# ADC_01_HYB.net
KiCad netlist of a schematic drawn in Altium Designer
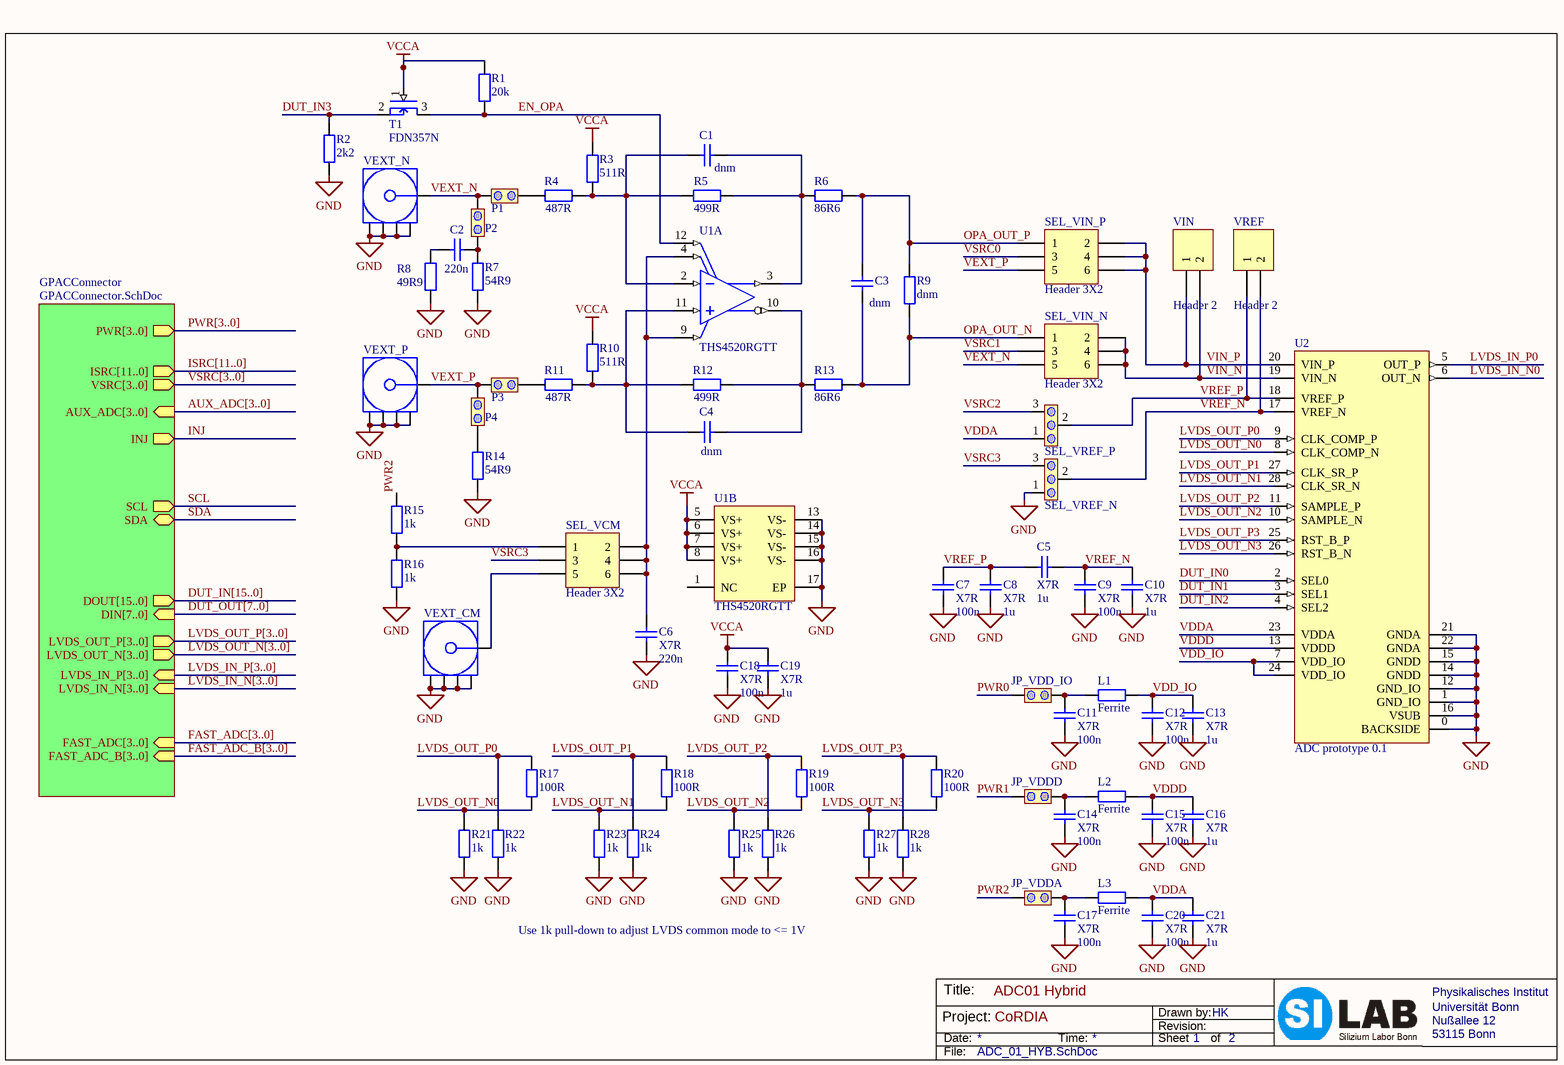
[diagram p0: ADC_01_HYB.SchDoc]

(export (version "E")
  (design (tool "Eeschema 10.0.6"))
  (components
    (comp (ref "C1")
      (value "dnm")
      (footprint "C0603_imp_N")
      (description "Capacitor")
      (fields (field (name "Comment") "X7R") (field (name "PUBLISHER") "Silab J.S."))
      (libsource (lib "Silab_Lib") (part "C"))
    )
    (comp (ref "C2")
      (value "220n")
      (footprint "C0603_imp_N")
      (description "Capacitor")
      (fields (field (name "Comment") "X7R") (field (name "PUBLISHER") "Silab J.S."))
      (libsource (lib "Silab_Lib") (part "C"))
    )
    (comp (ref "C3")
      (value "dnm")
      (footprint "C0603_imp_N")
      (description "Capacitor")
      (fields (field (name "Comment") "X7R") (field (name "PUBLISHER") "Silab J.S."))
      (libsource (lib "Silab_Lib") (part "C"))
    )
    (comp (ref "C4")
      (value "dnm")
      (footprint "C0603_imp_N")
      (description "Capacitor")
      (fields (field (name "Comment") "X7R") (field (name "PUBLISHER") "Silab J.S."))
      (libsource (lib "Silab_Lib") (part "C"))
    )
    (comp (ref "C5")
      (value "X7R")
      (footprint "C0603_imp_N")
      (description "Capacitor")
      (fields (field (name "ALTIUM_VALUE") "1u") (field (name "PUBLISHER") "Silab J.S."))
      (libsource (lib "Silab_Lib") (part "C"))
    )
    (comp (ref "C6")
      (value "X7R")
      (footprint "C0603_imp_N")
      (description "Capacitor")
      (fields (field (name "ALTIUM_VALUE") "220n") (field (name "PUBLISHER") "Silab J.S."))
      (libsource (lib "Silab_Lib") (part "C"))
    )
    (comp (ref "C7")
      (value "X7R")
      (footprint "C0603_imp_N")
      (description "Capacitor")
      (fields (field (name "ALTIUM_VALUE") "100n") (field (name "PUBLISHER") "Silab J.S."))
      (libsource (lib "Silab_Lib") (part "C"))
    )
    (comp (ref "C8")
      (value "X7R")
      (footprint "C0603_imp_N")
      (description "Capacitor")
      (fields (field (name "ALTIUM_VALUE") "1u") (field (name "PUBLISHER") "Silab J.S."))
      (libsource (lib "Silab_Lib") (part "C"))
    )
    (comp (ref "C9")
      (value "X7R")
      (footprint "C0603_imp_N")
      (description "Capacitor")
      (fields (field (name "ALTIUM_VALUE") "100n") (field (name "PUBLISHER") "Silab J.S."))
      (libsource (lib "Silab_Lib") (part "C"))
    )
    (comp (ref "C10")
      (value "X7R")
      (footprint "C0603_imp_N")
      (description "Capacitor")
      (fields (field (name "ALTIUM_VALUE") "1u") (field (name "PUBLISHER") "Silab J.S."))
      (libsource (lib "Silab_Lib") (part "C"))
    )
    (comp (ref "C11")
      (value "X7R")
      (footprint "C0603_imp_N")
      (description "Capacitor")
      (fields (field (name "ALTIUM_VALUE") "100n") (field (name "PUBLISHER") "Silab J.S."))
      (libsource (lib "Silab_Lib") (part "C"))
    )
    (comp (ref "C12")
      (value "X7R")
      (footprint "C0603_imp_N")
      (description "Capacitor")
      (fields (field (name "ALTIUM_VALUE") "100n") (field (name "PUBLISHER") "Silab J.S."))
      (libsource (lib "Silab_Lib") (part "C"))
    )
    (comp (ref "C13")
      (value "X7R")
      (footprint "C0603_imp_N")
      (description "Capacitor")
      (fields (field (name "ALTIUM_VALUE") "1u") (field (name "PUBLISHER") "Silab J.S."))
      (libsource (lib "Silab_Lib") (part "C"))
    )
    (comp (ref "C14")
      (value "X7R")
      (footprint "C0603_imp_N")
      (description "Capacitor")
      (fields (field (name "ALTIUM_VALUE") "100n") (field (name "PUBLISHER") "Silab J.S."))
      (libsource (lib "Silab_Lib") (part "C"))
    )
    (comp (ref "C15")
      (value "X7R")
      (footprint "C0603_imp_N")
      (description "Capacitor")
      (fields (field (name "ALTIUM_VALUE") "100n") (field (name "PUBLISHER") "Silab J.S."))
      (libsource (lib "Silab_Lib") (part "C"))
    )
    (comp (ref "C16")
      (value "X7R")
      (footprint "C0603_imp_N")
      (description "Capacitor")
      (fields (field (name "ALTIUM_VALUE") "1u") (field (name "PUBLISHER") "Silab J.S."))
      (libsource (lib "Silab_Lib") (part "C"))
    )
    (comp (ref "C17")
      (value "X7R")
      (footprint "C0603_imp_N")
      (description "Capacitor")
      (fields (field (name "ALTIUM_VALUE") "100n") (field (name "PUBLISHER") "Silab J.S."))
      (libsource (lib "Silab_Lib") (part "C"))
    )
    (comp (ref "C18")
      (value "X7R")
      (footprint "C0603_imp_N")
      (description "Capacitor")
      (fields (field (name "ALTIUM_VALUE") "100n") (field (name "PUBLISHER") "Silab J.S."))
      (libsource (lib "Silab_Lib") (part "C"))
    )
    (comp (ref "C19")
      (value "X7R")
      (footprint "C0603_imp_N")
      (description "Capacitor")
      (fields (field (name "ALTIUM_VALUE") "1u") (field (name "PUBLISHER") "Silab J.S."))
      (libsource (lib "Silab_Lib") (part "C"))
    )
    (comp (ref "C20")
      (value "X7R")
      (footprint "C0603_imp_N")
      (description "Capacitor")
      (fields (field (name "ALTIUM_VALUE") "100n") (field (name "PUBLISHER") "Silab J.S."))
      (libsource (lib "Silab_Lib") (part "C"))
    )
    (comp (ref "C21")
      (value "X7R")
      (footprint "C0603_imp_N")
      (description "Capacitor")
      (fields (field (name "ALTIUM_VALUE") "1u") (field (name "PUBLISHER") "Silab J.S."))
      (libsource (lib "Silab_Lib") (part "C"))
    )
    (comp (ref "JP_VDDA")
      (value "-")
      (footprint "CON 1x2 std")
      (description "Jumper, Solderbridge 1x2")
      (fields (field (name "PUBLISHER") "Silab C.H."))
      (libsource (lib "Silab_Lib") (part "JUMPER 1X2S"))
    )
    (comp (ref "JP_VDDD")
      (value "-")
      (footprint "CON 1x2 std")
      (description "Jumper, Solderbridge 1x2")
      (fields (field (name "PUBLISHER") "Silab C.H."))
      (libsource (lib "Silab_Lib") (part "JUMPER 1X2S"))
    )
    (comp (ref "JP_VDD_IO")
      (value "-")
      (footprint "CON 1x2 std")
      (description "Jumper, Solderbridge 1x2")
      (fields (field (name "PUBLISHER") "Silab C.H."))
      (libsource (lib "Silab_Lib") (part "JUMPER 1X2S"))
    )
    (comp (ref "L1")
      (value "Ferrite")
      (footprint "R0603_imp_N")
      (description "SMD Chip Resistor")
      (fields (field (name "Comment") "R") (field (name "PUBLISHER") "Silab J.S."))
      (libsource (lib "Silab_Lib") (part "R"))
    )
    (comp (ref "L2")
      (value "Ferrite")
      (footprint "R0603_imp_N")
      (description "SMD Chip Resistor")
      (fields (field (name "Comment") "R") (field (name "PUBLISHER") "Silab J.S."))
      (libsource (lib "Silab_Lib") (part "R"))
    )
    (comp (ref "L3")
      (value "Ferrite")
      (footprint "R0603_imp_N")
      (description "SMD Chip Resistor")
      (fields (field (name "Comment") "R") (field (name "PUBLISHER") "Silab J.S."))
      (libsource (lib "Silab_Lib") (part "R"))
    )
    (comp (ref "P1")
      (value "-")
      (footprint "CON 1x2 std")
      (description "Jumper, Solderbridge 1x2")
      (fields (field (name "PUBLISHER") "Silab C.H."))
      (libsource (lib "") (part "JUMPER 1X2S_2"))
    )
    (comp (ref "P2")
      (value "-")
      (footprint "CON 1x2 std")
      (description "Jumper, Solderbridge 1x2")
      (fields (field (name "PUBLISHER") "Silab C.H."))
      (libsource (lib "") (part "JUMPER 1X2S_1"))
    )
    (comp (ref "P3")
      (value "-")
      (footprint "CON 1x2 std")
      (description "Jumper, Solderbridge 1x2")
      (fields (field (name "PUBLISHER") "Silab C.H."))
      (libsource (lib "") (part "JUMPER 1X2S_2"))
    )
    (comp (ref "P4")
      (value "-")
      (footprint "CON 1x2 std")
      (description "Jumper, Solderbridge 1x2")
      (fields (field (name "PUBLISHER") "Silab C.H."))
      (libsource (lib "") (part "JUMPER 1X2S_1"))
    )
    (comp (ref "R1")
      (value "20k")
      (footprint "R0603_imp_N")
      (description "SMD Chip Resistor")
      (fields (field (name "Comment") "R") (field (name "PUBLISHER") "Silab J.S."))
      (libsource (lib "Silab_Lib") (part "R"))
    )
    (comp (ref "R2")
      (value "2k2")
      (footprint "R0603_imp_N")
      (description "SMD Chip Resistor")
      (fields (field (name "Comment") "R") (field (name "PUBLISHER") "Silab J.S."))
      (libsource (lib "Silab_Lib") (part "R"))
    )
    (comp (ref "R3")
      (value "511R")
      (footprint "R0603_imp_N")
      (description "SMD Chip Resistor")
      (fields (field (name "Comment") "R") (field (name "PUBLISHER") "Silab J.S."))
      (libsource (lib "Silab_Lib") (part "R"))
    )
    (comp (ref "R4")
      (value "487R")
      (footprint "R0603_imp_N")
      (description "SMD Chip Resistor")
      (fields (field (name "Comment") "R") (field (name "PUBLISHER") "Silab J.S."))
      (libsource (lib "Silab_Lib") (part "R"))
    )
    (comp (ref "R5")
      (value "499R")
      (footprint "R0603_imp_N")
      (description "SMD Chip Resistor")
      (fields (field (name "Comment") "R") (field (name "PUBLISHER") "Silab J.S."))
      (libsource (lib "Silab_Lib") (part "R"))
    )
    (comp (ref "R6")
      (value "86R6")
      (footprint "R0603_imp_N")
      (description "SMD Chip Resistor")
      (fields (field (name "Comment") "R") (field (name "PUBLISHER") "Silab J.S."))
      (libsource (lib "Silab_Lib") (part "R"))
    )
    (comp (ref "R7")
      (value "54R9")
      (footprint "R0603_imp_N")
      (description "SMD Chip Resistor")
      (fields (field (name "Comment") "R") (field (name "PUBLISHER") "Silab J.S."))
      (libsource (lib "Silab_Lib") (part "R"))
    )
    (comp (ref "R8")
      (value "49R9")
      (footprint "R0603_imp_N")
      (description "SMD Chip Resistor")
      (fields (field (name "Comment") "R") (field (name "PUBLISHER") "Silab J.S."))
      (libsource (lib "Silab_Lib") (part "R"))
    )
    (comp (ref "R9")
      (value "dnm")
      (footprint "R0603_imp_N")
      (description "SMD Chip Resistor")
      (fields (field (name "Comment") "R") (field (name "PUBLISHER") "Silab J.S."))
      (libsource (lib "Silab_Lib") (part "R"))
    )
    (comp (ref "R10")
      (value "511R")
      (footprint "R0603_imp_N")
      (description "SMD Chip Resistor")
      (fields (field (name "Comment") "R") (field (name "PUBLISHER") "Silab J.S."))
      (libsource (lib "Silab_Lib") (part "R"))
    )
    (comp (ref "R11")
      (value "487R")
      (footprint "R0603_imp_N")
      (description "SMD Chip Resistor")
      (fields (field (name "Comment") "R") (field (name "PUBLISHER") "Silab J.S."))
      (libsource (lib "Silab_Lib") (part "R"))
    )
    (comp (ref "R12")
      (value "499R")
      (footprint "R0603_imp_N")
      (description "SMD Chip Resistor")
      (fields (field (name "Comment") "R") (field (name "PUBLISHER") "Silab J.S."))
      (libsource (lib "Silab_Lib") (part "R"))
    )
    (comp (ref "R13")
      (value "86R6")
      (footprint "R0603_imp_N")
      (description "SMD Chip Resistor")
      (fields (field (name "Comment") "R") (field (name "PUBLISHER") "Silab J.S."))
      (libsource (lib "Silab_Lib") (part "R"))
    )
    (comp (ref "R14")
      (value "54R9")
      (footprint "R0603_imp_N")
      (description "SMD Chip Resistor")
      (fields (field (name "Comment") "R") (field (name "PUBLISHER") "Silab J.S."))
      (libsource (lib "Silab_Lib") (part "R"))
    )
    (comp (ref "R15")
      (value "1k")
      (footprint "R0603_imp_N")
      (description "SMD Chip Resistor")
      (fields (field (name "Comment") "R") (field (name "PUBLISHER") "Silab J.S."))
      (libsource (lib "Silab_Lib") (part "R"))
    )
    (comp (ref "R16")
      (value "1k")
      (footprint "R0603_imp_N")
      (description "SMD Chip Resistor")
      (fields (field (name "Comment") "R") (field (name "PUBLISHER") "Silab J.S."))
      (libsource (lib "Silab_Lib") (part "R"))
    )
    (comp (ref "R17")
      (value "100R")
      (footprint "R0603_imp_N")
      (description "SMD Chip Resistor")
      (fields (field (name "Comment") "R") (field (name "PUBLISHER") "Silab J.S."))
      (libsource (lib "Silab_Lib") (part "R"))
    )
    (comp (ref "R18")
      (value "100R")
      (footprint "R0603_imp_N")
      (description "SMD Chip Resistor")
      (fields (field (name "Comment") "R") (field (name "PUBLISHER") "Silab J.S."))
      (libsource (lib "Silab_Lib") (part "R"))
    )
    (comp (ref "R19")
      (value "100R")
      (footprint "R0603_imp_N")
      (description "SMD Chip Resistor")
      (fields (field (name "Comment") "R") (field (name "PUBLISHER") "Silab J.S."))
      (libsource (lib "Silab_Lib") (part "R"))
    )
    (comp (ref "R20")
      (value "100R")
      (footprint "R0603_imp_N")
      (description "SMD Chip Resistor")
      (fields (field (name "Comment") "R") (field (name "PUBLISHER") "Silab J.S."))
      (libsource (lib "Silab_Lib") (part "R"))
    )
    (comp (ref "R21")
      (value "1k")
      (footprint "R0603_imp_N")
      (description "SMD Chip Resistor")
      (fields (field (name "Comment") "R") (field (name "PUBLISHER") "Silab J.S."))
      (libsource (lib "Silab_Lib") (part "R"))
    )
    (comp (ref "R22")
      (value "1k")
      (footprint "R0603_imp_N")
      (description "SMD Chip Resistor")
      (fields (field (name "Comment") "R") (field (name "PUBLISHER") "Silab J.S."))
      (libsource (lib "Silab_Lib") (part "R"))
    )
    (comp (ref "R23")
      (value "1k")
      (footprint "R0603_imp_N")
      (description "SMD Chip Resistor")
      (fields (field (name "Comment") "R") (field (name "PUBLISHER") "Silab J.S."))
      (libsource (lib "Silab_Lib") (part "R"))
    )
    (comp (ref "R24")
      (value "1k")
      (footprint "R0603_imp_N")
      (description "SMD Chip Resistor")
      (fields (field (name "Comment") "R") (field (name "PUBLISHER") "Silab J.S."))
      (libsource (lib "Silab_Lib") (part "R"))
    )
    (comp (ref "R25")
      (value "1k")
      (footprint "R0603_imp_N")
      (description "SMD Chip Resistor")
      (fields (field (name "Comment") "R") (field (name "PUBLISHER") "Silab J.S."))
      (libsource (lib "Silab_Lib") (part "R"))
    )
    (comp (ref "R26")
      (value "1k")
      (footprint "R0603_imp_N")
      (description "SMD Chip Resistor")
      (fields (field (name "Comment") "R") (field (name "PUBLISHER") "Silab J.S."))
      (libsource (lib "Silab_Lib") (part "R"))
    )
    (comp (ref "R27")
      (value "1k")
      (footprint "R0603_imp_N")
      (description "SMD Chip Resistor")
      (fields (field (name "Comment") "R") (field (name "PUBLISHER") "Silab J.S."))
      (libsource (lib "Silab_Lib") (part "R"))
    )
    (comp (ref "R28")
      (value "1k")
      (footprint "R0603_imp_N")
      (description "SMD Chip Resistor")
      (fields (field (name "Comment") "R") (field (name "PUBLISHER") "Silab J.S."))
      (libsource (lib "Silab_Lib") (part "R"))
    )
    (comp (ref "SEL_VCM")
      (value "Header 3X2")
      (footprint "HDR2X3")
      (description "Header, 3-Pin, Dual row")
      (fields (field (name "PUBLISHER") "Altium Limited"))
      (libsource (lib "Miscellaneous Connectors") (part "Header 3X2"))
    )
    (comp (ref "SEL_VIN_N")
      (value "Header 3X2")
      (footprint "HDR2X3")
      (description "Header, 3-Pin, Dual row")
      (fields (field (name "PUBLISHER") "Altium Limited"))
      (libsource (lib "Miscellaneous Connectors") (part "Header 3X2"))
    )
    (comp (ref "SEL_VIN_P")
      (value "Header 3X2")
      (footprint "HDR2X3")
      (description "Header, 3-Pin, Dual row")
      (fields (field (name "PUBLISHER") "Altium Limited"))
      (libsource (lib "Miscellaneous Connectors") (part "Header 3X2"))
    )
    (comp (ref "SEL_VREF_N")
      (value "-")
      (footprint "HDR 1x3")
      (description "Jumper, Solderbridge 1x3")
      (fields (field (name "PUBLISHER") "Silab C.H."))
      (libsource (lib "Silab_Lib") (part "JUMPER 1X3S"))
    )
    (comp (ref "SEL_VREF_P")
      (value "-")
      (footprint "HDR 1x3")
      (description "Jumper, Solderbridge 1x3")
      (fields (field (name "PUBLISHER") "Silab C.H."))
      (libsource (lib "Silab_Lib") (part "JUMPER 1X3S"))
    )
    (comp (ref "T1")
      (value "FDN357N")
      (footprint "SOT23")
      (description "NMOS Transistor SMD")
      (fields (field (name "PUBLISHER") "Silab J.S."))
      (libsource (lib "Silab_Lib") (part "T NMOS"))
    )
    (comp (ref "U1")
      (value "THS4520RGTT")
      (footprint "RGT0016A_V")
      (fields (field (name "MANUFACTURER") "Texas Instruments"))
      (libsource (lib "Altium Content Vault") (part "TI-THS4508_4520-RGT16-1450X1450TP"))
    )
    (comp (ref "U2") (value "ADC prototype 0.1") (footprint "ADC01") (libsource (lib "ADC01") (part "ADC01")))
    (comp (ref "VEXT_CM")
      (value "-")
      (footprint "SMASTEHEND")
      (fields (field (name "PUBLISHER") "Silab C.H."))
      (libsource (lib "Silab_Lib") (part "SMA"))
    )
    (comp (ref "VEXT_N")
      (value "-")
      (footprint "SMASTEHEND")
      (fields (field (name "PUBLISHER") "Silab C.H."))
      (libsource (lib "Silab_Lib") (part "SMA"))
    )
    (comp (ref "VEXT_P")
      (value "-")
      (footprint "SMASTEHEND")
      (fields (field (name "PUBLISHER") "Silab C.H."))
      (libsource (lib "Silab_Lib") (part "SMA"))
    )
    (comp (ref "VIN")
      (value "Header 2")
      (footprint "HDR1X2")
      (description "Header, 2-Pin")
      (fields (field (name "PUBLISHER") "Altium Limited"))
      (libsource (lib "Miscellaneous Connectors") (part "Header 2"))
    )
    (comp (ref "VREF")
      (value "Header 2")
      (footprint "HDR1X2")
      (description "Header, 2-Pin")
      (fields (field (name "PUBLISHER") "Altium Limited"))
      (libsource (lib "Miscellaneous Connectors") (part "Header 2"))
    )
  )
  (nets
    (net (code "53") (name "/DUT_IN0") (class "Default")
      (node (ref "U2") (pin "2") (pinfunction "SEL0_2") (pintype "input"))
    )
    (net (code "54") (name "/DUT_IN1") (class "Default")
      (node (ref "U2") (pin "3") (pinfunction "SEL1_3") (pintype "input"))
    )
    (net (code "55") (name "/DUT_IN2") (class "Default")
      (node (ref "U2") (pin "4") (pinfunction "SEL2_4") (pintype "input"))
    )
    (net (code "56") (name "/DUT_IN3") (class "Default")
      (node (ref "R2") (pin "1") (pinfunction "1_1") (pintype "passive"))
      (node (ref "T1") (pin "2") (pinfunction "S_2") (pintype "passive"))
    )
    (net (code "59") (name "/EN_OPA") (class "Default")
      (node (ref "R1") (pin "2") (pinfunction "2_2") (pintype "passive"))
      (node (ref "T1") (pin "3") (pinfunction "D_3") (pintype "passive"))
      (node (ref "U1") (pin "12") (pinfunction "~{PD}_12") (pintype "input"))
    )
    (net (code "64") (name "/LVDS_IN_N0") (class "Default")
      (node (ref "U2") (pin "6") (pinfunction "OUT_N_6") (pintype "output"))
    )
    (net (code "66") (name "/LVDS_IN_P0") (class "Default")
      (node (ref "U2") (pin "5") (pinfunction "OUT_P_5") (pintype "output"))
    )
    (net (code "68") (name "/LVDS_OUT_N0") (class "Default")
      (node (ref "R17") (pin "2") (pinfunction "2_2") (pintype "passive"))
      (node (ref "R21") (pin "1") (pinfunction "1_1") (pintype "passive"))
      (node (ref "U2") (pin "8") (pinfunction "CLK_COMP_N_8") (pintype "input"))
    )
    (net (code "69") (name "/LVDS_OUT_N1") (class "Default")
      (node (ref "R18") (pin "2") (pinfunction "2_2") (pintype "passive"))
      (node (ref "R23") (pin "1") (pinfunction "1_1") (pintype "passive"))
      (node (ref "U2") (pin "28") (pinfunction "CLK_SR_N_28") (pintype "input"))
    )
    (net (code "70") (name "/LVDS_OUT_N2") (class "Default")
      (node (ref "R19") (pin "2") (pinfunction "2_2") (pintype "passive"))
      (node (ref "R25") (pin "1") (pinfunction "1_1") (pintype "passive"))
      (node (ref "U2") (pin "10") (pinfunction "SAMPLE_N_10") (pintype "input"))
    )
    (net (code "71") (name "/LVDS_OUT_N3") (class "Default")
      (node (ref "R20") (pin "2") (pinfunction "2_2") (pintype "passive"))
      (node (ref "R27") (pin "1") (pinfunction "1_1") (pintype "passive"))
      (node (ref "U2") (pin "26") (pinfunction "RST_B_N_26") (pintype "input"))
    )
    (net (code "73") (name "/LVDS_OUT_P0") (class "Default")
      (node (ref "R17") (pin "1") (pinfunction "1_1") (pintype "passive"))
      (node (ref "R22") (pin "1") (pinfunction "1_1") (pintype "passive"))
      (node (ref "U2") (pin "9") (pinfunction "CLK_COMP_P_9") (pintype "input"))
    )
    (net (code "74") (name "/LVDS_OUT_P1") (class "Default")
      (node (ref "R18") (pin "1") (pinfunction "1_1") (pintype "passive"))
      (node (ref "R24") (pin "1") (pinfunction "1_1") (pintype "passive"))
      (node (ref "U2") (pin "27") (pinfunction "CLK_SR_P_27") (pintype "input"))
    )
    (net (code "75") (name "/LVDS_OUT_P2") (class "Default")
      (node (ref "R19") (pin "1") (pinfunction "1_1") (pintype "passive"))
      (node (ref "R26") (pin "1") (pinfunction "1_1") (pintype "passive"))
      (node (ref "U2") (pin "11") (pinfunction "SAMPLE_P_11") (pintype "input"))
    )
    (net (code "76") (name "/LVDS_OUT_P3") (class "Default")
      (node (ref "R20") (pin "1") (pinfunction "1_1") (pintype "passive"))
      (node (ref "R28") (pin "1") (pinfunction "1_1") (pintype "passive"))
      (node (ref "U2") (pin "25") (pinfunction "RST_B_P_25") (pintype "input"))
    )
    (net (code "78") (name "/OPA_OUT_N") (class "Default")
      (node (ref "C3") (pin "2") (pinfunction "2_2") (pintype "passive"))
      (node (ref "R13") (pin "1") (pinfunction "1_1") (pintype "passive"))
      (node (ref "R9") (pin "1") (pinfunction "1_1") (pintype "passive"))
      (node (ref "SEL_VIN_N") (pin "1") (pinfunction "1_1") (pintype "passive"))
    )
    (net (code "79") (name "/OPA_OUT_P") (class "Default")
      (node (ref "C3") (pin "1") (pinfunction "1_1") (pintype "passive"))
      (node (ref "R6") (pin "1") (pinfunction "1_1") (pintype "passive"))
      (node (ref "R9") (pin "2") (pinfunction "2_2") (pintype "passive"))
      (node (ref "SEL_VIN_P") (pin "1") (pinfunction "1_1") (pintype "passive"))
    )
    (net (code "80") (name "/PWR0") (class "Default")
      (node (ref "JP_VDD_IO") (pin "1") (pinfunction "1_1") (pintype "passive"))
    )
    (net (code "81") (name "/PWR1") (class "Default")
      (node (ref "JP_VDDD") (pin "1") (pinfunction "1_1") (pintype "passive"))
    )
    (net (code "82") (name "/PWR2") (class "Default")
      (node (ref "JP_VDDA") (pin "1") (pinfunction "1_1") (pintype "passive"))
      (node (ref "R15") (pin "1") (pinfunction "1_1") (pintype "passive"))
    )
    (net (code "86") (name "/VDDA") (class "Default")
      (node (ref "C20") (pin "1") (pinfunction "1_1") (pintype "passive"))
      (node (ref "C21") (pin "1") (pinfunction "1_1") (pintype "passive"))
      (node (ref "L3") (pin "2") (pinfunction "2_2") (pintype "passive"))
      (node (ref "SEL_VREF_P") (pin "1") (pinfunction "1_1") (pintype "passive"))
      (node (ref "U2") (pin "23") (pinfunction "VDDA_23") (pintype "power_in"))
    )
    (net (code "87") (name "/VDDD") (class "Default")
      (node (ref "C15") (pin "1") (pinfunction "1_1") (pintype "passive"))
      (node (ref "C16") (pin "1") (pinfunction "1_1") (pintype "passive"))
      (node (ref "L2") (pin "2") (pinfunction "2_2") (pintype "passive"))
      (node (ref "U2") (pin "13") (pinfunction "VDDD_13") (pintype "power_in"))
    )
    (net (code "88") (name "/VDD_IO") (class "Default")
      (node (ref "C12") (pin "1") (pinfunction "1_1") (pintype "passive"))
      (node (ref "C13") (pin "1") (pinfunction "1_1") (pintype "passive"))
      (node (ref "L1") (pin "2") (pinfunction "2_2") (pintype "passive"))
      (node (ref "U2") (pin "24") (pinfunction "VDD_IO_24") (pintype "power_in"))
      (node (ref "U2") (pin "7") (pinfunction "VDD_IO_7") (pintype "power_in"))
    )
    (net (code "89") (name "/VEXT_N") (class "Default")
      (node (ref "P1") (pin "2") (pinfunction "2_2") (pintype "passive"))
      (node (ref "P2") (pin "2") (pinfunction "2_2") (pintype "passive"))
      (node (ref "SEL_VIN_N") (pin "5") (pinfunction "5_5") (pintype "passive"))
      (node (ref "VEXT_N") (pin "1") (pinfunction "Signal_1") (pintype "passive"))
    )
    (net (code "90") (name "/VEXT_P") (class "Default")
      (node (ref "P3") (pin "2") (pinfunction "2_2") (pintype "passive"))
      (node (ref "P4") (pin "2") (pinfunction "2_2") (pintype "passive"))
      (node (ref "SEL_VIN_P") (pin "5") (pinfunction "5_5") (pintype "passive"))
      (node (ref "VEXT_P") (pin "1") (pinfunction "Signal_1") (pintype "passive"))
    )
    (net (code "91") (name "/VIN_N") (class "Default")
      (node (ref "SEL_VIN_N") (pin "2") (pinfunction "2_2") (pintype "passive"))
      (node (ref "SEL_VIN_N") (pin "4") (pinfunction "4_4") (pintype "passive"))
      (node (ref "SEL_VIN_N") (pin "6") (pinfunction "6_6") (pintype "passive"))
      (node (ref "U2") (pin "19") (pinfunction "VIN_N_19") (pintype "passive"))
      (node (ref "VIN") (pin "2") (pinfunction "2_2") (pintype "passive"))
    )
    (net (code "92") (name "/VIN_P") (class "Default")
      (node (ref "SEL_VIN_P") (pin "2") (pinfunction "2_2") (pintype "passive"))
      (node (ref "SEL_VIN_P") (pin "4") (pinfunction "4_4") (pintype "passive"))
      (node (ref "SEL_VIN_P") (pin "6") (pinfunction "6_6") (pintype "passive"))
      (node (ref "U2") (pin "20") (pinfunction "VIN_P_20") (pintype "passive"))
      (node (ref "VIN") (pin "1") (pinfunction "1_1") (pintype "passive"))
    )
    (net (code "93") (name "/VREF_N") (class "Default")
      (node (ref "C10") (pin "1") (pinfunction "1_1") (pintype "passive"))
      (node (ref "C5") (pin "2") (pinfunction "2_2") (pintype "passive"))
      (node (ref "C9") (pin "1") (pinfunction "1_1") (pintype "passive"))
      (node (ref "SEL_VREF_N") (pin "2") (pinfunction "2_2") (pintype "passive"))
      (node (ref "U2") (pin "17") (pinfunction "VREF_N_17") (pintype "passive"))
      (node (ref "VREF") (pin "2") (pinfunction "2_2") (pintype "passive"))
    )
    (net (code "94") (name "/VREF_P") (class "Default")
      (node (ref "C5") (pin "1") (pinfunction "1_1") (pintype "passive"))
      (node (ref "C7") (pin "1") (pinfunction "1_1") (pintype "passive"))
      (node (ref "C8") (pin "1") (pinfunction "1_1") (pintype "passive"))
      (node (ref "SEL_VREF_P") (pin "2") (pinfunction "2_2") (pintype "passive"))
      (node (ref "U2") (pin "18") (pinfunction "VREF_P_18") (pintype "passive"))
      (node (ref "VREF") (pin "1") (pinfunction "1_1") (pintype "passive"))
    )
    (net (code "95") (name "/VSRC0") (class "Default")
      (node (ref "SEL_VIN_P") (pin "3") (pinfunction "3_3") (pintype "passive"))
    )
    (net (code "96") (name "/VSRC1") (class "Default")
      (node (ref "SEL_VIN_N") (pin "3") (pinfunction "3_3") (pintype "passive"))
    )
    (net (code "97") (name "/VSRC2") (class "Default")
      (node (ref "SEL_VREF_P") (pin "3") (pinfunction "3_3") (pintype "passive"))
    )
    (net (code "98") (name "/VSRC3") (class "Default")
      (node (ref "SEL_VCM") (pin "3") (pinfunction "3_3") (pintype "passive"))
      (node (ref "SEL_VREF_N") (pin "3") (pinfunction "3_3") (pintype "passive"))
    )
    (net (code "100") (name "GND") (class "Default")
      (node (ref "C10") (pin "2") (pinfunction "2_2") (pintype "passive"))
      (node (ref "C11") (pin "2") (pinfunction "2_2") (pintype "passive"))
      (node (ref "C12") (pin "2") (pinfunction "2_2") (pintype "passive"))
      (node (ref "C13") (pin "2") (pinfunction "2_2") (pintype "passive"))
      (node (ref "C14") (pin "2") (pinfunction "2_2") (pintype "passive"))
      (node (ref "C15") (pin "2") (pinfunction "2_2") (pintype "passive"))
      (node (ref "C16") (pin "2") (pinfunction "2_2") (pintype "passive"))
      (node (ref "C17") (pin "2") (pinfunction "2_2") (pintype "passive"))
      (node (ref "C18") (pin "2") (pinfunction "2_2") (pintype "passive"))
      (node (ref "C19") (pin "2") (pinfunction "2_2") (pintype "passive"))
      (node (ref "C20") (pin "2") (pinfunction "2_2") (pintype "passive"))
      (node (ref "C21") (pin "2") (pinfunction "2_2") (pintype "passive"))
      (node (ref "C6") (pin "2") (pinfunction "2_2") (pintype "passive"))
      (node (ref "C7") (pin "2") (pinfunction "2_2") (pintype "passive"))
      (node (ref "C8") (pin "2") (pinfunction "2_2") (pintype "passive"))
      (node (ref "C9") (pin "2") (pinfunction "2_2") (pintype "passive"))
      (node (ref "R14") (pin "2") (pinfunction "2_2") (pintype "passive"))
      (node (ref "R16") (pin "2") (pinfunction "2_2") (pintype "passive"))
      (node (ref "R2") (pin "2") (pinfunction "2_2") (pintype "passive"))
      (node (ref "R21") (pin "2") (pinfunction "2_2") (pintype "passive"))
      (node (ref "R22") (pin "2") (pinfunction "2_2") (pintype "passive"))
      (node (ref "R23") (pin "2") (pinfunction "2_2") (pintype "passive"))
      (node (ref "R24") (pin "2") (pinfunction "2_2") (pintype "passive"))
      (node (ref "R25") (pin "2") (pinfunction "2_2") (pintype "passive"))
      (node (ref "R26") (pin "2") (pinfunction "2_2") (pintype "passive"))
      (node (ref "R27") (pin "2") (pinfunction "2_2") (pintype "passive"))
      (node (ref "R28") (pin "2") (pinfunction "2_2") (pintype "passive"))
      (node (ref "R7") (pin "2") (pinfunction "2_2") (pintype "passive"))
      (node (ref "R8") (pin "2") (pinfunction "2_2") (pintype "passive"))
      (node (ref "SEL_VREF_N") (pin "1") (pinfunction "1_1") (pintype "passive"))
      (node (ref "U1") (pin "13") (pinfunction "VS-_13") (pintype "power_in"))
      (node (ref "U1") (pin "14") (pinfunction "VS-_14") (pintype "power_in"))
      (node (ref "U1") (pin "15") (pinfunction "VS-_15") (pintype "power_in"))
      (node (ref "U1") (pin "16") (pinfunction "VS-_16") (pintype "power_in"))
      (node (ref "U1") (pin "17") (pinfunction "EP_17") (pintype "passive"))
      (node (ref "U2") (pin "0") (pinfunction "BACKSIDE_0") (pintype "power_in"))
      (node (ref "U2") (pin "1") (pinfunction "GND_IO_1") (pintype "power_in"))
      (node (ref "U2") (pin "12") (pinfunction "GND_IO_12") (pintype "power_in"))
      (node (ref "U2") (pin "14") (pinfunction "GNDD_14") (pintype "power_in"))
      (node (ref "U2") (pin "15") (pinfunction "GNDD_15") (pintype "power_in"))
      (node (ref "U2") (pin "16") (pinfunction "VSUB_16") (pintype "power_in"))
      (node (ref "U2") (pin "21") (pinfunction "GNDA_21") (pintype "power_in"))
      (node (ref "U2") (pin "22") (pinfunction "GNDA_22") (pintype "power_in"))
      (node (ref "VEXT_CM") (pin "2") (pinfunction "GND_2") (pintype "power_in"))
      (node (ref "VEXT_CM") (pin "3") (pinfunction "GND_3") (pintype "power_in"))
      (node (ref "VEXT_CM") (pin "4") (pinfunction "GND_4") (pintype "power_in"))
      (node (ref "VEXT_CM") (pin "5") (pinfunction "GND_5") (pintype "power_in"))
      (node (ref "VEXT_N") (pin "2") (pinfunction "GND_2") (pintype "power_in"))
      (node (ref "VEXT_N") (pin "3") (pinfunction "GND_3") (pintype "power_in"))
      (node (ref "VEXT_N") (pin "4") (pinfunction "GND_4") (pintype "power_in"))
      (node (ref "VEXT_N") (pin "5") (pinfunction "GND_5") (pintype "power_in"))
      (node (ref "VEXT_P") (pin "2") (pinfunction "GND_2") (pintype "power_in"))
      (node (ref "VEXT_P") (pin "3") (pinfunction "GND_3") (pintype "power_in"))
      (node (ref "VEXT_P") (pin "4") (pinfunction "GND_4") (pintype "power_in"))
      (node (ref "VEXT_P") (pin "5") (pinfunction "GND_5") (pintype "power_in"))
    )
    (net (code "101") (name "Net-(C2-Pad1)") (class "Default")
      (node (ref "C2") (pin "1") (pinfunction "1_1") (pintype "passive"))
      (node (ref "R8") (pin "1") (pinfunction "1_1") (pintype "passive"))
    )
    (net (code "102") (name "Net-(C2-Pad2)") (class "Default")
      (node (ref "C2") (pin "2") (pinfunction "2_2") (pintype "passive"))
      (node (ref "P2") (pin "1") (pinfunction "1_1") (pintype "passive"))
      (node (ref "R7") (pin "1") (pinfunction "1_1") (pintype "passive"))
    )
    (net (code "103") (name "Net-(C6-Pad1)") (class "Default")
      (node (ref "C6") (pin "1") (pinfunction "1_1") (pintype "passive"))
      (node (ref "SEL_VCM") (pin "2") (pinfunction "2_2") (pintype "passive"))
      (node (ref "SEL_VCM") (pin "4") (pinfunction "4_4") (pintype "passive"))
      (node (ref "SEL_VCM") (pin "6") (pinfunction "6_6") (pintype "passive"))
      (node (ref "U1") (pin "4") (pinfunction "CM_4") (pintype "input"))
      (node (ref "U1") (pin "9") (pinfunction "CM_9") (pintype "input"))
    )
    (net (code "104") (name "Net-(C11-Pad1)") (class "Default")
      (node (ref "C11") (pin "1") (pinfunction "1_1") (pintype "passive"))
      (node (ref "JP_VDD_IO") (pin "2") (pinfunction "2_2") (pintype "passive"))
      (node (ref "L1") (pin "1") (pinfunction "1_1") (pintype "passive"))
    )
    (net (code "105") (name "Net-(C14-Pad1)") (class "Default")
      (node (ref "C14") (pin "1") (pinfunction "1_1") (pintype "passive"))
      (node (ref "JP_VDDD") (pin "2") (pinfunction "2_2") (pintype "passive"))
      (node (ref "L2") (pin "1") (pinfunction "1_1") (pintype "passive"))
    )
    (net (code "106") (name "Net-(C17-Pad1)") (class "Default")
      (node (ref "C17") (pin "1") (pinfunction "1_1") (pintype "passive"))
      (node (ref "JP_VDDA") (pin "2") (pinfunction "2_2") (pintype "passive"))
      (node (ref "L3") (pin "1") (pinfunction "1_1") (pintype "passive"))
    )
    (net (code "107") (name "Net-(P1-Pad1)") (class "Default")
      (node (ref "P1") (pin "1") (pinfunction "1_1") (pintype "passive"))
      (node (ref "R4") (pin "1") (pinfunction "1_1") (pintype "passive"))
    )
    (net (code "108") (name "Net-(P3-Pad1)") (class "Default")
      (node (ref "P3") (pin "1") (pinfunction "1_1") (pintype "passive"))
      (node (ref "R11") (pin "1") (pinfunction "1_1") (pintype "passive"))
    )
    (net (code "109") (name "Net-(P4-Pad1)") (class "Default")
      (node (ref "P4") (pin "1") (pinfunction "1_1") (pintype "passive"))
      (node (ref "R14") (pin "1") (pinfunction "1_1") (pintype "passive"))
    )
    (net (code "110") (name "Net-(R15-Pad2)") (class "Default")
      (node (ref "R15") (pin "2") (pinfunction "2_2") (pintype "passive"))
      (node (ref "R16") (pin "1") (pinfunction "1_1") (pintype "passive"))
      (node (ref "SEL_VCM") (pin "1") (pinfunction "1_1") (pintype "passive"))
    )
    (net (code "111") (name "Net-(U1A-VIN+)") (class "Default")
      (node (ref "C4") (pin "1") (pinfunction "1_1") (pintype "passive"))
      (node (ref "R10") (pin "2") (pinfunction "2_2") (pintype "passive"))
      (node (ref "R11") (pin "2") (pinfunction "2_2") (pintype "passive"))
      (node (ref "R12") (pin "1") (pinfunction "1_1") (pintype "passive"))
      (node (ref "U1") (pin "11") (pinfunction "VIN+_11") (pintype "input"))
    )
    (net (code "112") (name "Net-(U1A-VIN-)") (class "Default")
      (node (ref "C1") (pin "1") (pinfunction "1_1") (pintype "passive"))
      (node (ref "R3") (pin "2") (pinfunction "2_2") (pintype "passive"))
      (node (ref "R4") (pin "2") (pinfunction "2_2") (pintype "passive"))
      (node (ref "R5") (pin "1") (pinfunction "1_1") (pintype "passive"))
      (node (ref "U1") (pin "2") (pinfunction "VIN-_2") (pintype "input"))
    )
    (net (code "113") (name "Net-(U1A-VOUT+)") (class "Default")
      (node (ref "C1") (pin "2") (pinfunction "2_2") (pintype "passive"))
      (node (ref "R5") (pin "2") (pinfunction "2_2") (pintype "passive"))
      (node (ref "R6") (pin "2") (pinfunction "2_2") (pintype "passive"))
      (node (ref "U1") (pin "3") (pinfunction "VOUT+_3") (pintype "output"))
    )
    (net (code "114") (name "Net-(U1A-VOUT-)") (class "Default")
      (node (ref "C4") (pin "2") (pinfunction "2_2") (pintype "passive"))
      (node (ref "R12") (pin "2") (pinfunction "2_2") (pintype "passive"))
      (node (ref "R13") (pin "2") (pinfunction "2_2") (pintype "passive"))
      (node (ref "U1") (pin "10") (pinfunction "VOUT-_10") (pintype "output"))
    )
    (net (code "115") (name "Net-(VEXT_CM-Signal)") (class "Default")
      (node (ref "SEL_VCM") (pin "5") (pinfunction "5_5") (pintype "passive"))
      (node (ref "VEXT_CM") (pin "1") (pinfunction "Signal_1") (pintype "passive"))
    )
    (net (code "116") (name "VCCA") (class "Default")
      (node (ref "C18") (pin "1") (pinfunction "1_1") (pintype "passive"))
      (node (ref "C19") (pin "1") (pinfunction "1_1") (pintype "passive"))
      (node (ref "R1") (pin "1") (pinfunction "1_1") (pintype "passive"))
      (node (ref "R10") (pin "1") (pinfunction "1_1") (pintype "passive"))
      (node (ref "R3") (pin "1") (pinfunction "1_1") (pintype "passive"))
      (node (ref "T1") (pin "1") (pinfunction "G_1") (pintype "input"))
      (node (ref "U1") (pin "5") (pinfunction "VS+_5") (pintype "power_in"))
      (node (ref "U1") (pin "6") (pinfunction "VS+_6") (pintype "power_in"))
      (node (ref "U1") (pin "7") (pinfunction "VS+_7") (pintype "power_in"))
      (node (ref "U1") (pin "8") (pinfunction "VS+_8") (pintype "power_in"))
    )
    (net (code "117") (name "unconnected-(U1B-NC-Pad1)") (class "Default")
      (node (ref "U1") (pin "1") (pinfunction "NC_1") (pintype "passive"))
    )
  )
)
